# radio.net
KiCad netlist of a schematic drawn in Altium Designer
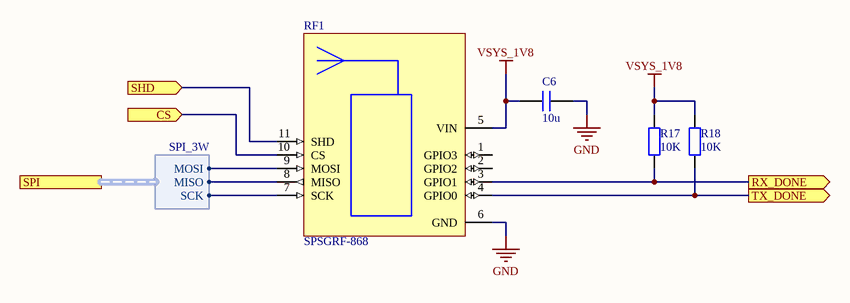
[diagram p0: radio.SchDoc]

(export (version "E")
  (design (tool "Eeschema 10.0.6"))
  (components
    (comp (ref "C6")
      (value "10u")
      (footprint "CAPC3216X14N")
      (description "Capacitor")
      (fields (field (name "Comment") "cap"))
      (libsource (lib "lib_passives") (part "cap"))
    )
    (comp (ref "R17")
      (value "10K")
      (footprint "RESC1005X04N")
      (description "Resistor")
      (fields (field (name "Comment") "res"))
      (libsource (lib "lib_passives") (part "res"))
    )
    (comp (ref "R18")
      (value "10K")
      (footprint "RESC1005X04N")
      (description "Resistor")
      (fields (field (name "Comment") "res"))
      (libsource (lib "lib_passives") (part "res"))
    )
    (comp (ref "RF1")
      (value "SPSGRF-868")
      (footprint "spsgrf")
      (description "Sub-GHz (868 or 915 MHz) low power programmable RF\r\ntransceiver modules")
      (libsource (lib "lib_st") (part "spsgrf-868"))
    )
  )
  (nets
    (net (code "2") (name "/CS") (class "Default")
      (node (ref "RF1") (pin "10") (pinfunction "CS_10") (pintype "input"))
    )
    (net (code "3") (name "/MISO") (class "Default")
      (node (ref "RF1") (pin "8") (pinfunction "MISO_8") (pintype "output"))
    )
    (net (code "4") (name "/MOSI") (class "Default")
      (node (ref "RF1") (pin "9") (pinfunction "MOSI_9") (pintype "input"))
    )
    (net (code "5") (name "/RX_DONE") (class "Default")
      (node (ref "R17") (pin "1") (pinfunction "1_1") (pintype "passive"))
      (node (ref "RF1") (pin "3") (pinfunction "GPIO1_3") (pintype "bidirectional"))
    )
    (net (code "6") (name "/SCK") (class "Default")
      (node (ref "RF1") (pin "7") (pinfunction "SCK_7") (pintype "input"))
    )
    (net (code "7") (name "/SHD") (class "Default")
      (node (ref "RF1") (pin "11") (pinfunction "SHD_11") (pintype "input"))
    )
    (net (code "8") (name "/TX_DONE") (class "Default")
      (node (ref "R18") (pin "1") (pinfunction "1_1") (pintype "passive"))
      (node (ref "RF1") (pin "4") (pinfunction "GPIO0_4") (pintype "bidirectional"))
    )
    (net (code "10") (name "GND") (class "Default")
      (node (ref "C6") (pin "2") (pinfunction "2_2") (pintype "passive"))
      (node (ref "RF1") (pin "6") (pinfunction "GND_6") (pintype "power_in"))
    )
    (net (code "11") (name "VSYS_1V8") (class "Default")
      (node (ref "C6") (pin "1") (pinfunction "1_1") (pintype "passive"))
      (node (ref "R17") (pin "2") (pinfunction "2_2") (pintype "passive"))
      (node (ref "R18") (pin "2") (pinfunction "2_2") (pintype "passive"))
      (node (ref "RF1") (pin "5") (pinfunction "VIN_5") (pintype "power_in"))
    )
    (net (code "12") (name "unconnected-(RF1-GPIO2-Pad2)") (class "Default")
      (node (ref "RF1") (pin "2") (pinfunction "GPIO2_2") (pintype "bidirectional"))
    )
    (net (code "13") (name "unconnected-(RF1-GPIO3-Pad1)") (class "Default")
      (node (ref "RF1") (pin "1") (pinfunction "GPIO3_1") (pintype "bidirectional"))
    )
  )
)
